# wemos-board.net
KiCad netlist of a schematic drawn in EAGLE
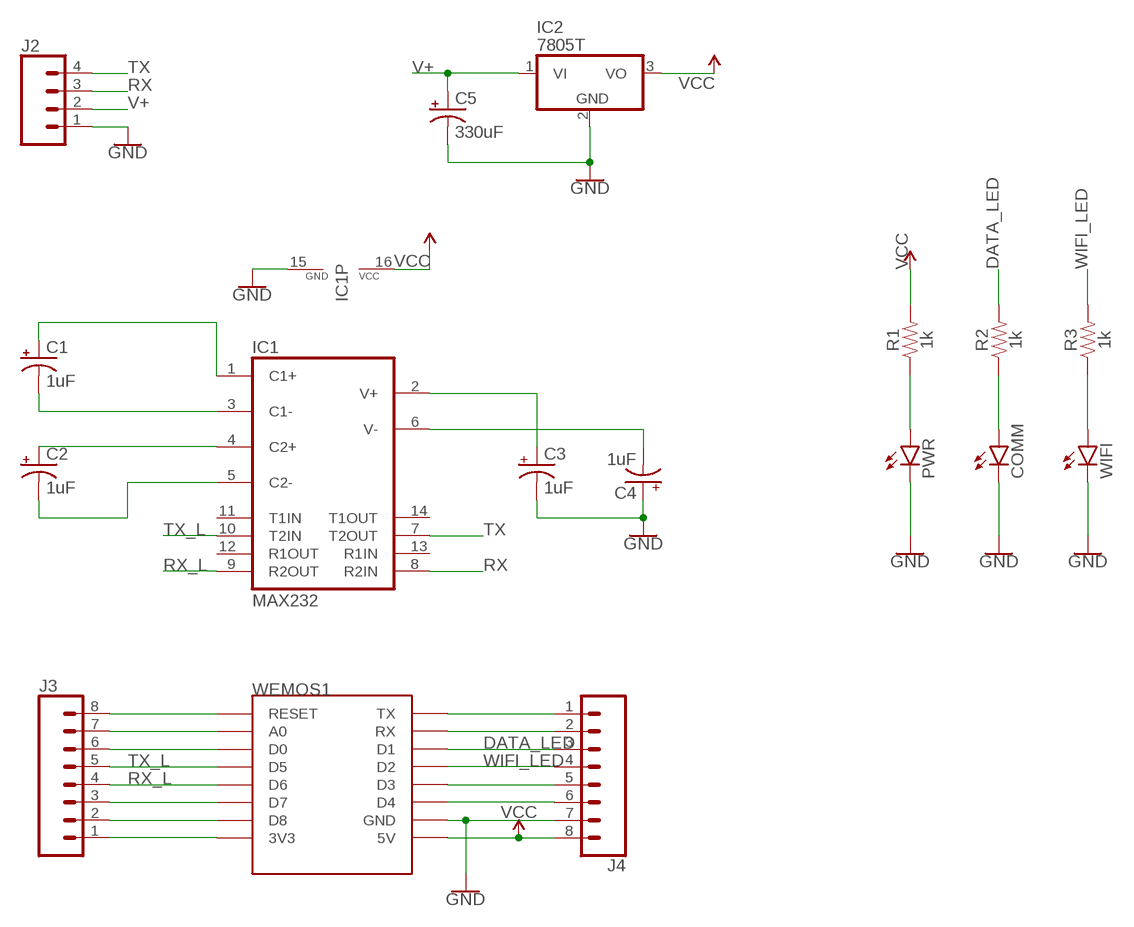
[diagram p0: schematic, sheet 1]

(export (version "E")
  (design (tool "Eeschema 10.0.6"))
  (components
    (comp (ref "C1")
      (value "1uF")
      (footprint "eagle-import:CPOL-RADIAL-2.5MM-6.5MM")
      (libsource (lib "eagle-import") (part "100UF-POLAR-RADIAL-2.5MM-25V-20%"))
    )
    (comp (ref "C2")
      (value "1uF")
      (footprint "eagle-import:CPOL-RADIAL-2.5MM-6.5MM")
      (libsource (lib "eagle-import") (part "100UF-POLAR-RADIAL-2.5MM-25V-20%"))
    )
    (comp (ref "C3")
      (value "1uF")
      (footprint "eagle-import:CPOL-RADIAL-2.5MM-6.5MM")
      (libsource (lib "eagle-import") (part "100UF-POLAR-RADIAL-2.5MM-25V-20%"))
    )
    (comp (ref "C4")
      (value "1uF")
      (footprint "eagle-import:CPOL-RADIAL-2.5MM-6.5MM")
      (libsource (lib "eagle-import") (part "100UF-POLAR-RADIAL-2.5MM-25V-20%"))
    )
    (comp (ref "C5")
      (value "330uF")
      (footprint "eagle-import:CPOL-RADIAL-2.5MM-6.5MM")
      (libsource (lib "eagle-import") (part "100UF-POLAR-RADIAL-2.5MM-25V-20%"))
    )
    (comp (ref "COMM")
      (value "LED3MM")
      (footprint "eagle-import:LED3MM")
      (libsource (lib "eagle-import") (part "LED3MM"))
    )
    (comp (ref "IC1")
      (value "MAX232")
      (footprint "eagle-import:DIL16")
      (fields (field (name "MF") "MAXIM") (field (name "MPN") "MAX232ACPE+"))
      (libsource (lib "eagle-import") (part "MAX232"))
    )
    (comp (ref "IC2")
      (value "7805T")
      (footprint "eagle-import:TO220H")
      (libsource (lib "eagle-import") (part "78T05"))
    )
    (comp (ref "J2")
      (value "CONN_04")
      (footprint "eagle-import:1X04")
      (libsource (lib "eagle-import") (part "CONN_04"))
    )
    (comp (ref "J3")
      (value "CONN_08\"")
      (footprint "eagle-import:1X08")
      (libsource (lib "eagle-import") (part "CONN_08{dblquote}"))
    )
    (comp (ref "J4")
      (value "CONN_08\"")
      (footprint "eagle-import:1X08")
      (libsource (lib "eagle-import") (part "CONN_08{dblquote}"))
    )
    (comp (ref "PWR")
      (value "LED3MM")
      (footprint "eagle-import:LED3MM")
      (libsource (lib "eagle-import") (part "LED3MM"))
    )
    (comp (ref "R1")
      (value "1k")
      (footprint "eagle-import:AXIAL-0.3-KIT")
      (libsource (lib "eagle-import") (part "1KOHM-HORIZ_KIT-1/4W-5%"))
    )
    (comp (ref "R2")
      (value "1k")
      (footprint "eagle-import:AXIAL-0.3-KIT")
      (libsource (lib "eagle-import") (part "1KOHM-HORIZ_KIT-1/4W-5%"))
    )
    (comp (ref "R3")
      (value "1k")
      (footprint "eagle-import:AXIAL-0.3-KIT")
      (libsource (lib "eagle-import") (part "1KOHM-HORIZ_KIT-1/4W-5%"))
    )
    (comp (ref "WEMOS1")
      (value "WEMOS-D1-MINI")
      (footprint "eagle-import:WEMOS-D1-MINI")
      (libsource (lib "eagle-import") (part "WEMOS-D1-MINI"))
    )
    (comp (ref "WIFI")
      (value "LED3MM")
      (footprint "eagle-import:LED3MM")
      (libsource (lib "eagle-import") (part "LED3MM"))
    )
  )
  (nets
    (net (code "1") (name "/DATA_LED") (class "Default")
      (node (ref "J4") (pin "3") (pinfunction "3_3") (pintype "passive"))
      (node (ref "R2") (pin "P$2") (pinfunction "2_P$2") (pintype "passive"))
      (node (ref "WEMOS1") (pin "D1") (pinfunction "D1_D1") (pintype "bidirectional"))
    )
    (net (code "2") (name "/RX") (class "Default")
      (node (ref "IC1") (pin "8") (pinfunction "R2IN_8") (pintype "input"))
      (node (ref "J2") (pin "3") (pinfunction "3_3") (pintype "passive"))
    )
    (net (code "3") (name "/RX_L") (class "Default")
      (node (ref "IC1") (pin "9") (pinfunction "R2OUT_9") (pintype "output"))
      (node (ref "J3") (pin "4") (pinfunction "4_4") (pintype "passive"))
      (node (ref "WEMOS1") (pin "D6") (pinfunction "D6_D6") (pintype "bidirectional"))
    )
    (net (code "4") (name "/TX") (class "Default")
      (node (ref "IC1") (pin "7") (pinfunction "T2OUT_7") (pintype "output"))
      (node (ref "J2") (pin "4") (pinfunction "4_4") (pintype "passive"))
    )
    (net (code "5") (name "/TX_L") (class "Default")
      (node (ref "IC1") (pin "10") (pinfunction "T2IN_10") (pintype "input"))
      (node (ref "J3") (pin "5") (pinfunction "5_5") (pintype "passive"))
      (node (ref "WEMOS1") (pin "D5") (pinfunction "D5_D5") (pintype "bidirectional"))
    )
    (net (code "6") (name "/V+") (class "Default")
      (node (ref "C5") (pin "1") (pinfunction "+_1") (pintype "passive"))
      (node (ref "IC2") (pin "1") (pinfunction "VI_1") (pintype "input"))
      (node (ref "J2") (pin "2") (pinfunction "2_2") (pintype "passive"))
    )
    (net (code "7") (name "/WIFI_LED") (class "Default")
      (node (ref "J4") (pin "4") (pinfunction "4_4") (pintype "passive"))
      (node (ref "R3") (pin "P$2") (pinfunction "2_P$2") (pintype "passive"))
      (node (ref "WEMOS1") (pin "D2") (pinfunction "D2_D2") (pintype "bidirectional"))
    )
    (net (code "8") (name "GND") (class "Default")
      (node (ref "C3") (pin "2") (pinfunction "-_2") (pintype "passive"))
      (node (ref "C4") (pin "1") (pinfunction "+_1") (pintype "passive"))
      (node (ref "C5") (pin "2") (pinfunction "-_2") (pintype "passive"))
      (node (ref "COMM") (pin "K") (pinfunction "C_K") (pintype "passive"))
      (node (ref "IC1") (pin "15") (pinfunction "GND_15") (pintype "power_in"))
      (node (ref "IC2") (pin "2") (pinfunction "GND_2") (pintype "passive"))
      (node (ref "J2") (pin "1") (pinfunction "1_1") (pintype "passive"))
      (node (ref "J4") (pin "7") (pinfunction "7_7") (pintype "passive"))
      (node (ref "PWR") (pin "K") (pinfunction "C_K") (pintype "passive"))
      (node (ref "WEMOS1") (pin "GND") (pinfunction "GND_GND") (pintype "bidirectional"))
      (node (ref "WIFI") (pin "K") (pinfunction "C_K") (pintype "passive"))
    )
    (net (code "9") (name "Net-(C1-+)") (class "Default")
      (node (ref "C1") (pin "1") (pinfunction "+_1") (pintype "passive"))
      (node (ref "IC1") (pin "1") (pinfunction "C1+_1") (pintype "bidirectional"))
    )
    (net (code "10") (name "Net-(C1--)") (class "Default")
      (node (ref "C1") (pin "2") (pinfunction "-_2") (pintype "passive"))
      (node (ref "IC1") (pin "3") (pinfunction "C1-_3") (pintype "bidirectional"))
    )
    (net (code "11") (name "Net-(C2-+)") (class "Default")
      (node (ref "C2") (pin "1") (pinfunction "+_1") (pintype "passive"))
      (node (ref "IC1") (pin "4") (pinfunction "C2+_4") (pintype "bidirectional"))
    )
    (net (code "12") (name "Net-(C2--)") (class "Default")
      (node (ref "C2") (pin "2") (pinfunction "-_2") (pintype "passive"))
      (node (ref "IC1") (pin "5") (pinfunction "C2-_5") (pintype "bidirectional"))
    )
    (net (code "13") (name "Net-(C3-+)") (class "Default")
      (node (ref "C3") (pin "1") (pinfunction "+_1") (pintype "passive"))
      (node (ref "IC1") (pin "2") (pinfunction "V+_2") (pintype "bidirectional"))
    )
    (net (code "14") (name "Net-(C4--)") (class "Default")
      (node (ref "C4") (pin "2") (pinfunction "-_2") (pintype "passive"))
      (node (ref "IC1") (pin "6") (pinfunction "V-_6") (pintype "bidirectional"))
    )
    (net (code "15") (name "Net-(J3-Pad1)") (class "Default")
      (node (ref "J3") (pin "1") (pinfunction "1_1") (pintype "passive"))
      (node (ref "WEMOS1") (pin "3V3") (pinfunction "3V3_3V3") (pintype "bidirectional"))
    )
    (net (code "16") (name "Net-(J3-Pad2)") (class "Default")
      (node (ref "J3") (pin "2") (pinfunction "2_2") (pintype "passive"))
      (node (ref "WEMOS1") (pin "D8") (pinfunction "D8_D8") (pintype "bidirectional"))
    )
    (net (code "17") (name "Net-(J3-Pad3)") (class "Default")
      (node (ref "J3") (pin "3") (pinfunction "3_3") (pintype "passive"))
      (node (ref "WEMOS1") (pin "D7") (pinfunction "D7_D7") (pintype "bidirectional"))
    )
    (net (code "18") (name "Net-(J3-Pad6)") (class "Default")
      (node (ref "J3") (pin "6") (pinfunction "6_6") (pintype "passive"))
      (node (ref "WEMOS1") (pin "D0") (pinfunction "D0_D0") (pintype "bidirectional"))
    )
    (net (code "19") (name "Net-(J3-Pad7)") (class "Default")
      (node (ref "J3") (pin "7") (pinfunction "7_7") (pintype "passive"))
      (node (ref "WEMOS1") (pin "A0") (pinfunction "A0_A0") (pintype "bidirectional"))
    )
    (net (code "20") (name "Net-(J3-Pad8)") (class "Default")
      (node (ref "J3") (pin "8") (pinfunction "8_8") (pintype "passive"))
      (node (ref "WEMOS1") (pin "RESET") (pinfunction "RESET_RESET") (pintype "bidirectional"))
    )
    (net (code "21") (name "Net-(J4-Pad1)") (class "Default")
      (node (ref "J4") (pin "1") (pinfunction "1_1") (pintype "passive"))
      (node (ref "WEMOS1") (pin "TX") (pinfunction "TX_TX") (pintype "bidirectional"))
    )
    (net (code "22") (name "Net-(J4-Pad2)") (class "Default")
      (node (ref "J4") (pin "2") (pinfunction "2_2") (pintype "passive"))
      (node (ref "WEMOS1") (pin "RX") (pinfunction "RX_RX") (pintype "bidirectional"))
    )
    (net (code "23") (name "Net-(J4-Pad5)") (class "Default")
      (node (ref "J4") (pin "5") (pinfunction "5_5") (pintype "passive"))
      (node (ref "WEMOS1") (pin "D3") (pinfunction "D3_D3") (pintype "bidirectional"))
    )
    (net (code "24") (name "Net-(J4-Pad6)") (class "Default")
      (node (ref "J4") (pin "6") (pinfunction "6_6") (pintype "passive"))
      (node (ref "WEMOS1") (pin "D4") (pinfunction "D4_D4") (pintype "bidirectional"))
    )
    (net (code "25") (name "Net-(R1-1)") (class "Default")
      (node (ref "PWR") (pin "A") (pinfunction "A_A") (pintype "passive"))
      (node (ref "R1") (pin "P$1") (pinfunction "1_P$1") (pintype "passive"))
    )
    (net (code "26") (name "Net-(R2-1)") (class "Default")
      (node (ref "COMM") (pin "A") (pinfunction "A_A") (pintype "passive"))
      (node (ref "R2") (pin "P$1") (pinfunction "1_P$1") (pintype "passive"))
    )
    (net (code "27") (name "Net-(R3-1)") (class "Default")
      (node (ref "R3") (pin "P$1") (pinfunction "1_P$1") (pintype "passive"))
      (node (ref "WIFI") (pin "A") (pinfunction "A_A") (pintype "passive"))
    )
    (net (code "28") (name "VCC") (class "Default")
      (node (ref "IC1") (pin "16") (pinfunction "VCC_16") (pintype "power_in"))
      (node (ref "IC2") (pin "3") (pinfunction "VO_3") (pintype "passive"))
      (node (ref "J4") (pin "8") (pinfunction "8_8") (pintype "passive"))
      (node (ref "R1") (pin "P$2") (pinfunction "2_P$2") (pintype "passive"))
      (node (ref "WEMOS1") (pin "5V") (pinfunction "5V_5V") (pintype "bidirectional"))
    )
    (net (code "29") (name "unconnected-(IC1A-R1IN-Pad13)") (class "Default")
      (node (ref "IC1") (pin "13") (pinfunction "R1IN_13") (pintype "input"))
    )
    (net (code "30") (name "unconnected-(IC1A-R1OUT-Pad12)") (class "Default")
      (node (ref "IC1") (pin "12") (pinfunction "R1OUT_12") (pintype "output"))
    )
    (net (code "31") (name "unconnected-(IC1A-T1IN-Pad11)") (class "Default")
      (node (ref "IC1") (pin "11") (pinfunction "T1IN_11") (pintype "input"))
    )
    (net (code "32") (name "unconnected-(IC1A-T1OUT-Pad14)") (class "Default")
      (node (ref "IC1") (pin "14") (pinfunction "T1OUT_14") (pintype "output"))
    )
  )
)
